# FP_Connectors.net
KiCad netlist of a schematic drawn in Altium Designer
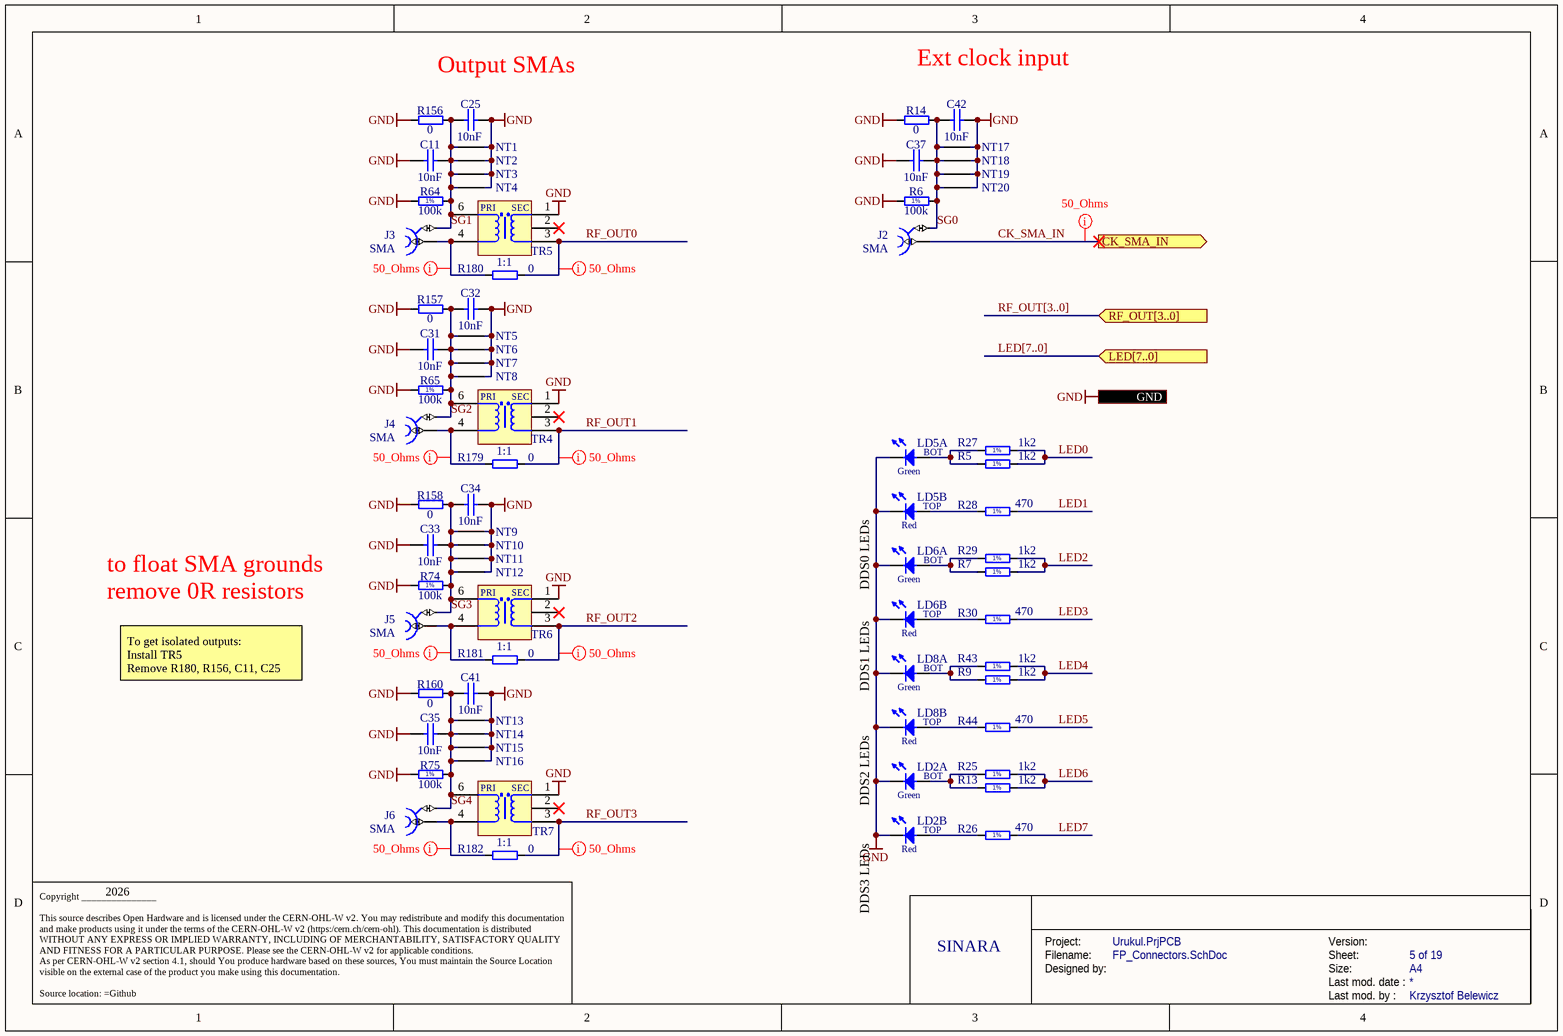
[diagram p0: FP_Connectors.SchDoc]

(export (version "E")
  (design (tool "Eeschema 10.0.6"))
  (components
    (comp (ref "C11")
      (value "10nF")
      (footprint "CAPC1005X55N")
      (description "Non-polarised capacitor")
      (fields
        (field (name "PART NUMBER") "CC0402_10NF_16V_10%_X7R")
        (field (name "VOLTAGE") "16V")
        (field (name "AUTHOR") "CERN DEM JLC")
      )
      (libsource (lib "Capacitors") (part "Capacitor - non polarized"))
    )
    (comp (ref "C25")
      (value "10nF")
      (footprint "CAPC1005X55N")
      (description "Non-polarised capacitor")
      (fields
        (field (name "PART NUMBER") "CC0402_10NF_16V_10%_X7R")
        (field (name "VOLTAGE") "16V")
        (field (name "AUTHOR") "CERN DEM JLC")
      )
      (libsource (lib "Capacitors") (part "Capacitor - non polarized"))
    )
    (comp (ref "C31")
      (value "10nF")
      (footprint "CAPC1005X55N")
      (description "Non-polarised capacitor")
      (fields
        (field (name "PART NUMBER") "CC0402_10NF_16V_10%_X7R")
        (field (name "VOLTAGE") "16V")
        (field (name "AUTHOR") "CERN DEM JLC")
      )
      (libsource (lib "Capacitors") (part "Capacitor - non polarized"))
    )
    (comp (ref "C32")
      (value "10nF")
      (footprint "CAPC1005X55N")
      (description "Non-polarised capacitor")
      (fields
        (field (name "PART NUMBER") "CC0402_10NF_16V_10%_X7R")
        (field (name "VOLTAGE") "16V")
        (field (name "AUTHOR") "CERN DEM JLC")
      )
      (libsource (lib "Capacitors") (part "Capacitor - non polarized"))
    )
    (comp (ref "C33")
      (value "10nF")
      (footprint "CAPC1005X55N")
      (description "Non-polarised capacitor")
      (fields
        (field (name "PART NUMBER") "CC0402_10NF_16V_10%_X7R")
        (field (name "VOLTAGE") "16V")
        (field (name "AUTHOR") "CERN DEM JLC")
      )
      (libsource (lib "Capacitors") (part "Capacitor - non polarized"))
    )
    (comp (ref "C34")
      (value "10nF")
      (footprint "CAPC1005X55N")
      (description "Non-polarised capacitor")
      (fields
        (field (name "PART NUMBER") "CC0402_10NF_16V_10%_X7R")
        (field (name "VOLTAGE") "16V")
        (field (name "AUTHOR") "CERN DEM JLC")
      )
      (libsource (lib "Capacitors") (part "Capacitor - non polarized"))
    )
    (comp (ref "C35")
      (value "10nF")
      (footprint "CAPC1005X55N")
      (description "Non-polarised capacitor")
      (fields
        (field (name "PART NUMBER") "CC0402_10NF_16V_10%_X7R")
        (field (name "VOLTAGE") "16V")
        (field (name "AUTHOR") "CERN DEM JLC")
      )
      (libsource (lib "Capacitors") (part "Capacitor - non polarized"))
    )
    (comp (ref "C37")
      (value "10nF")
      (footprint "CAPC1005X55N")
      (description "Non-polarised capacitor")
      (fields
        (field (name "PART NUMBER") "CC0402_10NF_16V_10%_X7R")
        (field (name "VOLTAGE") "16V")
        (field (name "AUTHOR") "CERN DEM JLC")
      )
      (libsource (lib "Capacitors") (part "Capacitor - non polarized"))
    )
    (comp (ref "C41")
      (value "10nF")
      (footprint "CAPC1005X55N")
      (description "Non-polarised capacitor")
      (fields
        (field (name "PART NUMBER") "CC0402_10NF_16V_10%_X7R")
        (field (name "VOLTAGE") "16V")
        (field (name "AUTHOR") "CERN DEM JLC")
      )
      (libsource (lib "Capacitors") (part "Capacitor - non polarized"))
    )
    (comp (ref "C42")
      (value "10nF")
      (footprint "CAPC1005X55N")
      (description "Non-polarised capacitor")
      (fields
        (field (name "PART NUMBER") "CC0402_10NF_16V_10%_X7R")
        (field (name "VOLTAGE") "16V")
        (field (name "AUTHOR") "CERN DEM JLC")
      )
      (libsource (lib "Capacitors") (part "Capacitor - non polarized"))
    )
    (comp (ref "J2")
      (value "SMA")
      (footprint "DELOCK_65848")
      (description "50 Ohm Through Hole SMA Right Angle PCB Jack")
      (fields
        (field (name "PART NUMBER") "DELOCK_65848")
        (field (name "MANUFACTURER") "DELOCK")
        (field (name "AUTHOR") "GK")
      )
      (libsource (lib "Connectors") (part "CON_SMA_DELOCK_65848"))
    )
    (comp (ref "J3")
      (value "SMA")
      (footprint "DELOCK_65848")
      (description "50 Ohm Through Hole SMA Right Angle PCB Jack")
      (fields
        (field (name "PART NUMBER") "DELOCK_65848")
        (field (name "MANUFACTURER") "DELOCK")
        (field (name "AUTHOR") "GK")
      )
      (libsource (lib "Connectors") (part "CON_SMA_DELOCK_65848"))
    )
    (comp (ref "J4")
      (value "SMA")
      (footprint "DELOCK_65848")
      (description "50 Ohm Through Hole SMA Right Angle PCB Jack")
      (fields
        (field (name "PART NUMBER") "DELOCK_65848")
        (field (name "MANUFACTURER") "DELOCK")
        (field (name "AUTHOR") "GK")
      )
      (libsource (lib "Connectors") (part "CON_SMA_DELOCK_65848"))
    )
    (comp (ref "J5")
      (value "SMA")
      (footprint "DELOCK_65848")
      (description "50 Ohm Through Hole SMA Right Angle PCB Jack")
      (fields
        (field (name "PART NUMBER") "DELOCK_65848")
        (field (name "MANUFACTURER") "DELOCK")
        (field (name "AUTHOR") "GK")
      )
      (libsource (lib "Connectors") (part "CON_SMA_DELOCK_65848"))
    )
    (comp (ref "J6")
      (value "SMA")
      (footprint "DELOCK_65848")
      (description "50 Ohm Through Hole SMA Right Angle PCB Jack")
      (fields
        (field (name "PART NUMBER") "DELOCK_65848")
        (field (name "MANUFACTURER") "DELOCK")
        (field (name "AUTHOR") "GK")
      )
      (libsource (lib "Connectors") (part "CON_SMA_DELOCK_65848"))
    )
    (comp (ref "LD2")
      (value "Red/Green")
      (footprint "LED_DIALIGHT_571-0112F")
      (description "2x LED  Botom Green, Top Red")
      (fields
        (field (name "PART NUMBER") "LED_DIALIGHT_571-0112F")
        (field (name "MANUFACTURER") "DIALIGHT")
        (field (name "AUTHOR") "CERN DEM JLC")
      )
      (libsource (lib "ICs And Semiconductors") (part "LED x2 G-1C2A-BOT_R-3C4A-TOP"))
    )
    (comp (ref "LD5")
      (value "Red/Green")
      (footprint "LED_DIALIGHT_571-0112F")
      (description "2x LED  Botom Green, Top Red")
      (fields
        (field (name "PART NUMBER") "LED_DIALIGHT_571-0112F")
        (field (name "MANUFACTURER") "DIALIGHT")
        (field (name "AUTHOR") "CERN DEM JLC")
      )
      (libsource (lib "ICs And Semiconductors") (part "LED x2 G-1C2A-BOT_R-3C4A-TOP"))
    )
    (comp (ref "LD6")
      (value "Red/Green")
      (footprint "LED_DIALIGHT_571-0112F")
      (description "2x LED  Botom Green, Top Red")
      (fields
        (field (name "PART NUMBER") "LED_DIALIGHT_571-0112F")
        (field (name "MANUFACTURER") "DIALIGHT")
        (field (name "AUTHOR") "CERN DEM JLC")
      )
      (libsource (lib "ICs And Semiconductors") (part "LED x2 G-1C2A-BOT_R-3C4A-TOP"))
    )
    (comp (ref "LD8")
      (value "Red/Green")
      (footprint "LED_DIALIGHT_571-0112F")
      (description "2x LED  Botom Green, Top Red")
      (fields
        (field (name "PART NUMBER") "LED_DIALIGHT_571-0112F")
        (field (name "MANUFACTURER") "DIALIGHT")
        (field (name "AUTHOR") "CERN DEM JLC")
      )
      (libsource (lib "ICs And Semiconductors") (part "LED x2 G-1C2A-BOT_R-3C4A-TOP"))
    )
    (comp (ref "NT1")
      (value "Net Tie")
      (footprint "Net Tie")
      (fields (field (name "AUTHOR") "CERN DEM JLC"))
      (libsource (lib "Eletro-mechanical") (part "Net Tie"))
    )
    (comp (ref "NT2")
      (value "Net Tie")
      (footprint "Net Tie")
      (fields (field (name "AUTHOR") "CERN DEM JLC"))
      (libsource (lib "Eletro-mechanical") (part "Net Tie"))
    )
    (comp (ref "NT3")
      (value "Net Tie")
      (footprint "Net Tie")
      (fields (field (name "AUTHOR") "CERN DEM JLC"))
      (libsource (lib "Eletro-mechanical") (part "Net Tie"))
    )
    (comp (ref "NT4")
      (value "Net Tie")
      (footprint "Net Tie")
      (fields (field (name "AUTHOR") "CERN DEM JLC"))
      (libsource (lib "Eletro-mechanical") (part "Net Tie"))
    )
    (comp (ref "NT5")
      (value "Net Tie")
      (footprint "Net Tie")
      (fields (field (name "AUTHOR") "CERN DEM JLC"))
      (libsource (lib "Eletro-mechanical") (part "Net Tie"))
    )
    (comp (ref "NT6")
      (value "Net Tie")
      (footprint "Net Tie")
      (fields (field (name "AUTHOR") "CERN DEM JLC"))
      (libsource (lib "Eletro-mechanical") (part "Net Tie"))
    )
    (comp (ref "NT7")
      (value "Net Tie")
      (footprint "Net Tie")
      (fields (field (name "AUTHOR") "CERN DEM JLC"))
      (libsource (lib "Eletro-mechanical") (part "Net Tie"))
    )
    (comp (ref "NT8")
      (value "Net Tie")
      (footprint "Net Tie")
      (fields (field (name "AUTHOR") "CERN DEM JLC"))
      (libsource (lib "Eletro-mechanical") (part "Net Tie"))
    )
    (comp (ref "NT9")
      (value "Net Tie")
      (footprint "Net Tie")
      (fields (field (name "AUTHOR") "CERN DEM JLC"))
      (libsource (lib "Eletro-mechanical") (part "Net Tie"))
    )
    (comp (ref "NT10")
      (value "Net Tie")
      (footprint "Net Tie")
      (fields (field (name "AUTHOR") "CERN DEM JLC"))
      (libsource (lib "Eletro-mechanical") (part "Net Tie"))
    )
    (comp (ref "NT11")
      (value "Net Tie")
      (footprint "Net Tie")
      (fields (field (name "AUTHOR") "CERN DEM JLC"))
      (libsource (lib "Eletro-mechanical") (part "Net Tie"))
    )
    (comp (ref "NT12")
      (value "Net Tie")
      (footprint "Net Tie")
      (fields (field (name "AUTHOR") "CERN DEM JLC"))
      (libsource (lib "Eletro-mechanical") (part "Net Tie"))
    )
    (comp (ref "NT13")
      (value "Net Tie")
      (footprint "Net Tie")
      (fields (field (name "AUTHOR") "CERN DEM JLC"))
      (libsource (lib "Eletro-mechanical") (part "Net Tie"))
    )
    (comp (ref "NT14")
      (value "Net Tie")
      (footprint "Net Tie")
      (fields (field (name "AUTHOR") "CERN DEM JLC"))
      (libsource (lib "Eletro-mechanical") (part "Net Tie"))
    )
    (comp (ref "NT15")
      (value "Net Tie")
      (footprint "Net Tie")
      (fields (field (name "AUTHOR") "CERN DEM JLC"))
      (libsource (lib "Eletro-mechanical") (part "Net Tie"))
    )
    (comp (ref "NT16")
      (value "Net Tie")
      (footprint "Net Tie")
      (fields (field (name "AUTHOR") "CERN DEM JLC"))
      (libsource (lib "Eletro-mechanical") (part "Net Tie"))
    )
    (comp (ref "NT17")
      (value "Net Tie")
      (footprint "Net Tie")
      (fields (field (name "AUTHOR") "CERN DEM JLC"))
      (libsource (lib "Eletro-mechanical") (part "Net Tie"))
    )
    (comp (ref "NT18")
      (value "Net Tie")
      (footprint "Net Tie")
      (fields (field (name "AUTHOR") "CERN DEM JLC"))
      (libsource (lib "Eletro-mechanical") (part "Net Tie"))
    )
    (comp (ref "NT19")
      (value "Net Tie")
      (footprint "Net Tie")
      (fields (field (name "AUTHOR") "CERN DEM JLC"))
      (libsource (lib "Eletro-mechanical") (part "Net Tie"))
    )
    (comp (ref "NT20")
      (value "Net Tie")
      (footprint "Net Tie")
      (fields (field (name "AUTHOR") "CERN DEM JLC"))
      (libsource (lib "Eletro-mechanical") (part "Net Tie"))
    )
    (comp (ref "R5")
      (value "1k2")
      (footprint "RESC1608X55N")
      (description "Resistor - 1%")
      (fields
        (field (name "PART NUMBER") "R0603_1K2_1%_0.1W_100PPM")
        (field (name "POWER") "0.1W")
        (field (name "AUTHOR") "CERN DEM JLC")
      )
      (libsource (lib "Resistors") (part "Resistor - 1%"))
    )
    (comp (ref "R6")
      (value "100k")
      (footprint "RESC1005X40N")
      (description "Resistor - 1%")
      (fields
        (field (name "PART NUMBER") "R0402_100K_1%_0.0625W_100PPM")
        (field (name "MANUFACTURER") "GENERIC")
        (field (name "AUTHOR") "CERN DEM JLC")
      )
      (libsource (lib "Resistors") (part "Resistor - 1%"))
    )
    (comp (ref "R7")
      (value "1k2")
      (footprint "RESC1608X55N")
      (description "Resistor - 1%")
      (fields
        (field (name "PART NUMBER") "R0603_1K2_1%_0.1W_100PPM")
        (field (name "POWER") "0.1W")
        (field (name "AUTHOR") "CERN DEM JLC")
      )
      (libsource (lib "Resistors") (part "Resistor - 1%"))
    )
    (comp (ref "R9")
      (value "1k2")
      (footprint "RESC1608X55N")
      (description "Resistor - 1%")
      (fields
        (field (name "PART NUMBER") "R0603_1K2_1%_0.1W_100PPM")
        (field (name "POWER") "0.1W")
        (field (name "AUTHOR") "CERN DEM JLC")
      )
      (libsource (lib "Resistors") (part "Resistor - 1%"))
    )
    (comp (ref "R13")
      (value "1k2")
      (footprint "RESC1608X55N")
      (description "Resistor - 1%")
      (fields
        (field (name "PART NUMBER") "R0603_1K2_1%_0.1W_100PPM")
        (field (name "POWER") "0.1W")
        (field (name "AUTHOR") "CERN DEM JLC")
      )
      (libsource (lib "Resistors") (part "Resistor - 1%"))
    )
    (comp (ref "R14")
      (value "0")
      (footprint "RESC1608X55N")
      (description "Resistor")
      (fields
        (field (name "PART NUMBER") "R0603_0R_JUMPER")
        (field (name "MANUFACTURER") "GENERIC")
        (field (name "AUTHOR") "CERN DEM JLC")
      )
      (libsource (lib "Resistors") (part "Resistor"))
    )
    (comp (ref "R25")
      (value "1k2")
      (footprint "RESC1608X55N")
      (description "Resistor - 1%")
      (fields
        (field (name "PART NUMBER") "R0603_1K2_1%_0.1W_100PPM")
        (field (name "POWER") "0.1W")
        (field (name "AUTHOR") "CERN DEM JLC")
      )
      (libsource (lib "Resistors") (part "Resistor - 1%"))
    )
    (comp (ref "R26")
      (value "470")
      (footprint "RESC1005X40N")
      (description "Resistor - 1%")
      (fields
        (field (name "PART NUMBER") "R0402_470R_1%_0.0625W_100PPM")
        (field (name "POWER") "0.0625W")
        (field (name "AUTHOR") "CERN DEM JLC")
      )
      (libsource (lib "Resistors") (part "Resistor - 1%"))
    )
    (comp (ref "R27")
      (value "1k2")
      (footprint "RESC1608X55N")
      (description "Resistor - 1%")
      (fields
        (field (name "PART NUMBER") "R0603_1K2_1%_0.1W_100PPM")
        (field (name "POWER") "0.1W")
        (field (name "AUTHOR") "CERN DEM JLC")
      )
      (libsource (lib "Resistors") (part "Resistor - 1%"))
    )
    (comp (ref "R28")
      (value "470")
      (footprint "RESC1005X40N")
      (description "Resistor - 1%")
      (fields
        (field (name "PART NUMBER") "R0402_470R_1%_0.0625W_100PPM")
        (field (name "POWER") "0.0625W")
        (field (name "AUTHOR") "CERN DEM JLC")
      )
      (libsource (lib "Resistors") (part "Resistor - 1%"))
    )
    (comp (ref "R29")
      (value "1k2")
      (footprint "RESC1608X55N")
      (description "Resistor - 1%")
      (fields
        (field (name "PART NUMBER") "R0603_1K2_1%_0.1W_100PPM")
        (field (name "POWER") "0.1W")
        (field (name "AUTHOR") "CERN DEM JLC")
      )
      (libsource (lib "Resistors") (part "Resistor - 1%"))
    )
    (comp (ref "R30")
      (value "470")
      (footprint "RESC1005X40N")
      (description "Resistor - 1%")
      (fields
        (field (name "PART NUMBER") "R0402_470R_1%_0.0625W_100PPM")
        (field (name "POWER") "0.0625W")
        (field (name "AUTHOR") "CERN DEM JLC")
      )
      (libsource (lib "Resistors") (part "Resistor - 1%"))
    )
    (comp (ref "R43")
      (value "1k2")
      (footprint "RESC1608X55N")
      (description "Resistor - 1%")
      (fields
        (field (name "PART NUMBER") "R0603_1K2_1%_0.1W_100PPM")
        (field (name "POWER") "0.1W")
        (field (name "AUTHOR") "CERN DEM JLC")
      )
      (libsource (lib "Resistors") (part "Resistor - 1%"))
    )
    (comp (ref "R44")
      (value "470")
      (footprint "RESC1005X40N")
      (description "Resistor - 1%")
      (fields
        (field (name "PART NUMBER") "R0402_470R_1%_0.0625W_100PPM")
        (field (name "POWER") "0.0625W")
        (field (name "AUTHOR") "CERN DEM JLC")
      )
      (libsource (lib "Resistors") (part "Resistor - 1%"))
    )
    (comp (ref "R64")
      (value "100k")
      (footprint "RESC1005X40N")
      (description "Resistor - 1%")
      (fields
        (field (name "PART NUMBER") "R0402_100K_1%_0.0625W_100PPM")
        (field (name "MANUFACTURER") "GENERIC")
        (field (name "AUTHOR") "CERN DEM JLC")
      )
      (libsource (lib "Resistors") (part "Resistor - 1%"))
    )
    (comp (ref "R65")
      (value "100k")
      (footprint "RESC1005X40N")
      (description "Resistor - 1%")
      (fields
        (field (name "PART NUMBER") "R0402_100K_1%_0.0625W_100PPM")
        (field (name "MANUFACTURER") "GENERIC")
        (field (name "AUTHOR") "CERN DEM JLC")
      )
      (libsource (lib "Resistors") (part "Resistor - 1%"))
    )
    (comp (ref "R74")
      (value "100k")
      (footprint "RESC1005X40N")
      (description "Resistor - 1%")
      (fields
        (field (name "PART NUMBER") "R0402_100K_1%_0.0625W_100PPM")
        (field (name "MANUFACTURER") "GENERIC")
        (field (name "AUTHOR") "CERN DEM JLC")
      )
      (libsource (lib "Resistors") (part "Resistor - 1%"))
    )
    (comp (ref "R75")
      (value "100k")
      (footprint "RESC1005X40N")
      (description "Resistor - 1%")
      (fields
        (field (name "PART NUMBER") "R0402_100K_1%_0.0625W_100PPM")
        (field (name "MANUFACTURER") "GENERIC")
        (field (name "AUTHOR") "CERN DEM JLC")
      )
      (libsource (lib "Resistors") (part "Resistor - 1%"))
    )
    (comp (ref "R156")
      (value "0")
      (footprint "RESC1608X55N")
      (description "Resistor")
      (fields
        (field (name "PART NUMBER") "R0603_0R_JUMPER")
        (field (name "MANUFACTURER") "GENERIC")
        (field (name "AUTHOR") "CERN DEM JLC")
      )
      (libsource (lib "Resistors") (part "Resistor"))
    )
    (comp (ref "R157")
      (value "0")
      (footprint "RESC1608X55N")
      (description "Resistor")
      (fields
        (field (name "PART NUMBER") "R0603_0R_JUMPER")
        (field (name "MANUFACTURER") "GENERIC")
        (field (name "AUTHOR") "CERN DEM JLC")
      )
      (libsource (lib "Resistors") (part "Resistor"))
    )
    (comp (ref "R158")
      (value "0")
      (footprint "RESC1608X55N")
      (description "Resistor")
      (fields
        (field (name "PART NUMBER") "R0603_0R_JUMPER")
        (field (name "MANUFACTURER") "GENERIC")
        (field (name "AUTHOR") "CERN DEM JLC")
      )
      (libsource (lib "Resistors") (part "Resistor"))
    )
    (comp (ref "R160")
      (value "0")
      (footprint "RESC1608X55N")
      (description "Resistor")
      (fields
        (field (name "PART NUMBER") "R0603_0R_JUMPER")
        (field (name "MANUFACTURER") "GENERIC")
        (field (name "AUTHOR") "CERN DEM JLC")
      )
      (libsource (lib "Resistors") (part "Resistor"))
    )
    (comp (ref "R179")
      (value "0")
      (footprint "RESC1005X40N")
      (description "Resistor")
      (fields
        (field (name "PART NUMBER") "R0402_0R_JUMPER")
        (field (name "MANUFACTURER") "GENERIC")
        (field (name "AUTHOR") "CERN DEM JLC")
      )
      (libsource (lib "Resistors") (part "Resistor"))
    )
    (comp (ref "R180")
      (value "0")
      (footprint "RESC1005X40N")
      (description "Resistor")
      (fields
        (field (name "PART NUMBER") "R0402_0R_JUMPER")
        (field (name "MANUFACTURER") "GENERIC")
        (field (name "AUTHOR") "CERN DEM JLC")
      )
      (libsource (lib "Resistors") (part "Resistor"))
    )
    (comp (ref "R181")
      (value "0")
      (footprint "RESC1005X40N")
      (description "Resistor")
      (fields
        (field (name "PART NUMBER") "R0402_0R_JUMPER")
        (field (name "MANUFACTURER") "GENERIC")
        (field (name "AUTHOR") "CERN DEM JLC")
      )
      (libsource (lib "Resistors") (part "Resistor"))
    )
    (comp (ref "R182")
      (value "0")
      (footprint "RESC1005X40N")
      (description "Resistor")
      (fields
        (field (name "PART NUMBER") "R0402_0R_JUMPER")
        (field (name "MANUFACTURER") "GENERIC")
        (field (name "AUTHOR") "CERN DEM JLC")
      )
      (libsource (lib "Resistors") (part "Resistor"))
    )
    (comp (ref "TR4")
      (value "1:1")
      (footprint "XFMR_MINI-CIRCUITS_AT224-1")
      (description "50 Ohm 1.5 To 500MHz RF Transformers")
      (fields
        (field (name "PART NUMBER") "XFMR_MINI-CIRCUITS_TC1-1+")
        (field (name "MANUFACTURER") "MINI-CIRCUITS")
        (field (name "AUTHOR") "CERN DEM JLC")
      )
      (libsource (lib "Inductors & Transformers") (part "XFMR_MINI-CIRCUITS_TC1-1+"))
    )
    (comp (ref "TR5")
      (value "1:1")
      (footprint "XFMR_MINI-CIRCUITS_AT224-1")
      (description "50 Ohm 1.5 To 500MHz RF Transformers")
      (fields
        (field (name "PART NUMBER") "XFMR_MINI-CIRCUITS_TC1-1+")
        (field (name "MANUFACTURER") "MINI-CIRCUITS")
        (field (name "AUTHOR") "CERN DEM JLC")
      )
      (libsource (lib "Inductors & Transformers") (part "XFMR_MINI-CIRCUITS_TC1-1+"))
    )
    (comp (ref "TR6")
      (value "1:1")
      (footprint "XFMR_MINI-CIRCUITS_AT224-1")
      (description "50 Ohm 1.5 To 500MHz RF Transformers")
      (fields
        (field (name "PART NUMBER") "XFMR_MINI-CIRCUITS_TC1-1+")
        (field (name "MANUFACTURER") "MINI-CIRCUITS")
        (field (name "AUTHOR") "CERN DEM JLC")
      )
      (libsource (lib "Inductors & Transformers") (part "XFMR_MINI-CIRCUITS_TC1-1+"))
    )
    (comp (ref "TR7")
      (value "1:1")
      (footprint "XFMR_MINI-CIRCUITS_AT224-1")
      (description "50 Ohm 1.5 To 500MHz RF Transformers")
      (fields
        (field (name "PART NUMBER") "XFMR_MINI-CIRCUITS_TC1-1+")
        (field (name "MANUFACTURER") "MINI-CIRCUITS")
        (field (name "AUTHOR") "CERN DEM JLC")
      )
      (libsource (lib "Inductors & Transformers") (part "XFMR_MINI-CIRCUITS_TC1-1+"))
    )
  )
  (nets
    (net (code "1") (name "/CK_SMA_IN") (class "Default")
      (node (ref "J2") (pin "1") (pinfunction "1_1") (pintype "bidirectional+no_connect"))
    )
    (net (code "2") (name "/LED0") (class "Default")
      (node (ref "R27") (pin "2") (pinfunction "2_2") (pintype "passive"))
      (node (ref "R5") (pin "2") (pinfunction "2_2") (pintype "passive"))
    )
    (net (code "3") (name "/LED1") (class "Default")
      (node (ref "R28") (pin "1") (pinfunction "1_1") (pintype "passive"))
    )
    (net (code "4") (name "/LED2") (class "Default")
      (node (ref "R29") (pin "2") (pinfunction "2_2") (pintype "passive"))
      (node (ref "R7") (pin "2") (pinfunction "2_2") (pintype "passive"))
    )
    (net (code "5") (name "/LED3") (class "Default")
      (node (ref "R30") (pin "1") (pinfunction "1_1") (pintype "passive"))
    )
    (net (code "6") (name "/LED4") (class "Default")
      (node (ref "R43") (pin "2") (pinfunction "2_2") (pintype "passive"))
      (node (ref "R9") (pin "2") (pinfunction "2_2") (pintype "passive"))
    )
    (net (code "7") (name "/LED5") (class "Default")
      (node (ref "R44") (pin "1") (pinfunction "1_1") (pintype "passive"))
    )
    (net (code "8") (name "/LED6") (class "Default")
      (node (ref "R13") (pin "2") (pinfunction "2_2") (pintype "passive"))
      (node (ref "R25") (pin "2") (pinfunction "2_2") (pintype "passive"))
    )
    (net (code "9") (name "/LED7") (class "Default")
      (node (ref "R26") (pin "1") (pinfunction "1_1") (pintype "passive"))
    )
    (net (code "11") (name "/RF_OUT0") (class "Default")
      (node (ref "R180") (pin "2") (pinfunction "2_2") (pintype "passive"))
      (node (ref "TR5") (pin "3") (pinfunction "S_3") (pintype "passive"))
    )
    (net (code "12") (name "/RF_OUT1") (class "Default")
      (node (ref "R179") (pin "2") (pinfunction "2_2") (pintype "passive"))
      (node (ref "TR4") (pin "3") (pinfunction "S_3") (pintype "passive"))
    )
    (net (code "13") (name "/RF_OUT2") (class "Default")
      (node (ref "R181") (pin "2") (pinfunction "2_2") (pintype "passive"))
      (node (ref "TR6") (pin "3") (pinfunction "S_3") (pintype "passive"))
    )
    (net (code "14") (name "/RF_OUT3") (class "Default")
      (node (ref "R182") (pin "2") (pinfunction "2_2") (pintype "passive"))
      (node (ref "TR7") (pin "3") (pinfunction "S_3") (pintype "passive"))
    )
    (net (code "16") (name "/SG0") (class "Default")
      (node (ref "C37") (pin "1") (pinfunction "1_1") (pintype "passive"))
      (node (ref "C42") (pin "2") (pinfunction "2_2") (pintype "passive"))
      (node (ref "J2") (pin "2") (pinfunction "2_2") (pintype "bidirectional"))
      (node (ref "NT17") (pin "1") (pinfunction "1_1") (pintype "bidirectional"))
      (node (ref "NT18") (pin "1") (pinfunction "1_1") (pintype "bidirectional"))
      (node (ref "NT19") (pin "1") (pinfunction "1_1") (pintype "bidirectional"))
      (node (ref "NT20") (pin "1") (pinfunction "1_1") (pintype "bidirectional"))
      (node (ref "R14") (pin "2") (pinfunction "2_2") (pintype "passive"))
      (node (ref "R6") (pin "2") (pinfunction "2_2") (pintype "passive"))
    )
    (net (code "17") (name "/SG1") (class "Default")
      (node (ref "C11") (pin "1") (pinfunction "1_1") (pintype "passive"))
      (node (ref "C25") (pin "2") (pinfunction "2_2") (pintype "passive"))
      (node (ref "J3") (pin "2") (pinfunction "2_2") (pintype "bidirectional"))
      (node (ref "NT1") (pin "1") (pinfunction "1_1") (pintype "bidirectional"))
      (node (ref "NT2") (pin "1") (pinfunction "1_1") (pintype "bidirectional"))
      (node (ref "NT3") (pin "1") (pinfunction "1_1") (pintype "bidirectional"))
      (node (ref "NT4") (pin "1") (pinfunction "1_1") (pintype "bidirectional"))
      (node (ref "R156") (pin "2") (pinfunction "2_2") (pintype "passive"))
      (node (ref "R64") (pin "2") (pinfunction "2_2") (pintype "passive"))
      (node (ref "TR5") (pin "6") (pinfunction "PDOT_6") (pintype "passive"))
    )
    (net (code "18") (name "/SG2") (class "Default")
      (node (ref "C31") (pin "1") (pinfunction "1_1") (pintype "passive"))
      (node (ref "C32") (pin "2") (pinfunction "2_2") (pintype "passive"))
      (node (ref "J4") (pin "2") (pinfunction "2_2") (pintype "bidirectional"))
      (node (ref "NT5") (pin "1") (pinfunction "1_1") (pintype "bidirectional"))
      (node (ref "NT6") (pin "1") (pinfunction "1_1") (pintype "bidirectional"))
      (node (ref "NT7") (pin "1") (pinfunction "1_1") (pintype "bidirectional"))
      (node (ref "NT8") (pin "1") (pinfunction "1_1") (pintype "bidirectional"))
      (node (ref "R157") (pin "2") (pinfunction "2_2") (pintype "passive"))
      (node (ref "R65") (pin "2") (pinfunction "2_2") (pintype "passive"))
      (node (ref "TR4") (pin "6") (pinfunction "PDOT_6") (pintype "passive"))
    )
    (net (code "19") (name "/SG3") (class "Default")
      (node (ref "C33") (pin "1") (pinfunction "1_1") (pintype "passive"))
      (node (ref "C34") (pin "2") (pinfunction "2_2") (pintype "passive"))
      (node (ref "J5") (pin "2") (pinfunction "2_2") (pintype "bidirectional"))
      (node (ref "NT10") (pin "1") (pinfunction "1_1") (pintype "bidirectional"))
      (node (ref "NT11") (pin "1") (pinfunction "1_1") (pintype "bidirectional"))
      (node (ref "NT12") (pin "1") (pinfunction "1_1") (pintype "bidirectional"))
      (node (ref "NT9") (pin "1") (pinfunction "1_1") (pintype "bidirectional"))
      (node (ref "R158") (pin "2") (pinfunction "2_2") (pintype "passive"))
      (node (ref "R74") (pin "2") (pinfunction "2_2") (pintype "passive"))
      (node (ref "TR6") (pin "6") (pinfunction "PDOT_6") (pintype "passive"))
    )
    (net (code "20") (name "/SG4") (class "Default")
      (node (ref "C35") (pin "1") (pinfunction "1_1") (pintype "passive"))
      (node (ref "C41") (pin "2") (pinfunction "2_2") (pintype "passive"))
      (node (ref "J6") (pin "2") (pinfunction "2_2") (pintype "bidirectional"))
      (node (ref "NT13") (pin "1") (pinfunction "1_1") (pintype "bidirectional"))
      (node (ref "NT14") (pin "1") (pinfunction "1_1") (pintype "bidirectional"))
      (node (ref "NT15") (pin "1") (pinfunction "1_1") (pintype "bidirectional"))
      (node (ref "NT16") (pin "1") (pinfunction "1_1") (pintype "bidirectional"))
      (node (ref "R160") (pin "2") (pinfunction "2_2") (pintype "passive"))
      (node (ref "R75") (pin "2") (pinfunction "2_2") (pintype "passive"))
      (node (ref "TR7") (pin "6") (pinfunction "PDOT_6") (pintype "passive"))
    )
    (net (code "21") (name "GND") (class "Default")
      (node (ref "C11") (pin "2") (pinfunction "2_2") (pintype "passive"))
      (node (ref "C25") (pin "1") (pinfunction "1_1") (pintype "passive"))
      (node (ref "C31") (pin "2") (pinfunction "2_2") (pintype "passive"))
      (node (ref "C32") (pin "1") (pinfunction "1_1") (pintype "passive"))
      (node (ref "C33") (pin "2") (pinfunction "2_2") (pintype "passive"))
      (node (ref "C34") (pin "1") (pinfunction "1_1") (pintype "passive"))
      (node (ref "C35") (pin "2") (pinfunction "2_2") (pintype "passive"))
      (node (ref "C37") (pin "2") (pinfunction "2_2") (pintype "passive"))
      (node (ref "C41") (pin "1") (pinfunction "1_1") (pintype "passive"))
      (node (ref "C42") (pin "1") (pinfunction "1_1") (pintype "passive"))
      (node (ref "LD2") (pin "1") (pinfunction "C_1") (pintype "passive"))
      (node (ref "LD2") (pin "3") (pinfunction "C_3") (pintype "passive"))
      (node (ref "LD5") (pin "1") (pinfunction "C_1") (pintype "passive"))
      (node (ref "LD5") (pin "3") (pinfunction "C_3") (pintype "passive"))
      (node (ref "LD6") (pin "1") (pinfunction "C_1") (pintype "passive"))
      (node (ref "LD6") (pin "3") (pinfunction "C_3") (pintype "passive"))
      (node (ref "LD8") (pin "1") (pinfunction "C_1") (pintype "passive"))
      (node (ref "LD8") (pin "3") (pinfunction "C_3") (pintype "passive"))
      (node (ref "NT1") (pin "2") (pinfunction "2_2") (pintype "bidirectional"))
      (node (ref "NT10") (pin "2") (pinfunction "2_2") (pintype "bidirectional"))
      (node (ref "NT11") (pin "2") (pinfunction "2_2") (pintype "bidirectional"))
      (node (ref "NT12") (pin "2") (pinfunction "2_2") (pintype "bidirectional"))
      (node (ref "NT13") (pin "2") (pinfunction "2_2") (pintype "bidirectional"))
      (node (ref "NT14") (pin "2") (pinfunction "2_2") (pintype "bidirectional"))
      (node (ref "NT15") (pin "2") (pinfunction "2_2") (pintype "bidirectional"))
      (node (ref "NT16") (pin "2") (pinfunction "2_2") (pintype "bidirectional"))
      (node (ref "NT17") (pin "2") (pinfunction "2_2") (pintype "bidirectional"))
      (node (ref "NT18") (pin "2") (pinfunction "2_2") (pintype "bidirectional"))
      (node (ref "NT19") (pin "2") (pinfunction "2_2") (pintype "bidirectional"))
      (node (ref "NT2") (pin "2") (pinfunction "2_2") (pintype "bidirectional"))
      (node (ref "NT20") (pin "2") (pinfunction "2_2") (pintype "bidirectional"))
      (node (ref "NT3") (pin "2") (pinfunction "2_2") (pintype "bidirectional"))
      (node (ref "NT4") (pin "2") (pinfunction "2_2") (pintype "bidirectional"))
      (node (ref "NT5") (pin "2") (pinfunction "2_2") (pintype "bidirectional"))
      (node (ref "NT6") (pin "2") (pinfunction "2_2") (pintype "bidirectional"))
      (node (ref "NT7") (pin "2") (pinfunction "2_2") (pintype "bidirectional"))
      (node (ref "NT8") (pin "2") (pinfunction "2_2") (pintype "bidirectional"))
      (node (ref "NT9") (pin "2") (pinfunction "2_2") (pintype "bidirectional"))
      (node (ref "R14") (pin "1") (pinfunction "1_1") (pintype "passive"))
      (node (ref "R156") (pin "1") (pinfunction "1_1") (pintype "passive"))
      (node (ref "R157") (pin "1") (pinfunction "1_1") (pintype "passive"))
      (node (ref "R158") (pin "1") (pinfunction "1_1") (pintype "passive"))
      (node (ref "R160") (pin "1") (pinfunction "1_1") (pintype "passive"))
      (node (ref "R6") (pin "1") (pinfunction "1_1") (pintype "passive"))
      (node (ref "R64") (pin "1") (pinfunction "1_1") (pintype "passive"))
      (node (ref "R65") (pin "1") (pinfunction "1_1") (pintype "passive"))
      (node (ref "R74") (pin "1") (pinfunction "1_1") (pintype "passive"))
      (node (ref "R75") (pin "1") (pinfunction "1_1") (pintype "passive"))
      (node (ref "TR4") (pin "1") (pinfunction "SDOT_1") (pintype "passive"))
      (node (ref "TR5") (pin "1") (pinfunction "SDOT_1") (pintype "passive"))
      (node (ref "TR6") (pin "1") (pinfunction "SDOT_1") (pintype "passive"))
      (node (ref "TR7") (pin "1") (pinfunction "SDOT_1") (pintype "passive"))
    )
    (net (code "22") (name "Net-(LD2A-A)") (class "Default")
      (node (ref "LD2") (pin "2") (pinfunction "A_2") (pintype "passive"))
      (node (ref "R13") (pin "1") (pinfunction "1_1") (pintype "passive"))
      (node (ref "R25") (pin "1") (pinfunction "1_1") (pintype "passive"))
    )
    (net (code "23") (name "Net-(LD2B-A)") (class "Default")
      (node (ref "LD2") (pin "4") (pinfunction "A_4") (pintype "passive"))
      (node (ref "R26") (pin "2") (pinfunction "2_2") (pintype "passive"))
    )
    (net (code "24") (name "Net-(LD5A-A)") (class "Default")
      (node (ref "LD5") (pin "2") (pinfunction "A_2") (pintype "passive"))
      (node (ref "R27") (pin "1") (pinfunction "1_1") (pintype "passive"))
      (node (ref "R5") (pin "1") (pinfunction "1_1") (pintype "passive"))
    )
    (net (code "25") (name "Net-(LD5B-A)") (class "Default")
      (node (ref "LD5") (pin "4") (pinfunction "A_4") (pintype "passive"))
      (node (ref "R28") (pin "2") (pinfunction "2_2") (pintype "passive"))
    )
    (net (code "26") (name "Net-(LD6A-A)") (class "Default")
      (node (ref "LD6") (pin "2") (pinfunction "A_2") (pintype "passive"))
      (node (ref "R29") (pin "1") (pinfunction "1_1") (pintype "passive"))
      (node (ref "R7") (pin "1") (pinfunction "1_1") (pintype "passive"))
    )
    (net (code "27") (name "Net-(LD6B-A)") (class "Default")
      (node (ref "LD6") (pin "4") (pinfunction "A_4") (pintype "passive"))
      (node (ref "R30") (pin "2") (pinfunction "2_2") (pintype "passive"))
    )
    (net (code "28") (name "Net-(LD8A-A)") (class "Default")
      (node (ref "LD8") (pin "2") (pinfunction "A_2") (pintype "passive"))
      (node (ref "R43") (pin "1") (pinfunction "1_1") (pintype "passive"))
      (node (ref "R9") (pin "1") (pinfunction "1_1") (pintype "passive"))
    )
    (net (code "29") (name "Net-(LD8B-A)") (class "Default")
      (node (ref "LD8") (pin "4") (pinfunction "A_4") (pintype "passive"))
      (node (ref "R44") (pin "2") (pinfunction "2_2") (pintype "passive"))
    )
    (net (code "30") (name "Net-(TR4-P)") (class "Default")
      (node (ref "J4") (pin "1") (pinfunction "1_1") (pintype "bidirectional"))
      (node (ref "R179") (pin "1") (pinfunction "1_1") (pintype "passive"))
      (node (ref "TR4") (pin "4") (pinfunction "P_4") (pintype "passive"))
    )
    (net (code "31") (name "Net-(TR5-P)") (class "Default")
      (node (ref "J3") (pin "1") (pinfunction "1_1") (pintype "bidirectional"))
      (node (ref "R180") (pin "1") (pinfunction "1_1") (pintype "passive"))
      (node (ref "TR5") (pin "4") (pinfunction "P_4") (pintype "passive"))
    )
    (net (code "32") (name "Net-(TR6-P)") (class "Default")
      (node (ref "J5") (pin "1") (pinfunction "1_1") (pintype "bidirectional"))
      (node (ref "R181") (pin "1") (pinfunction "1_1") (pintype "passive"))
      (node (ref "TR6") (pin "4") (pinfunction "P_4") (pintype "passive"))
    )
    (net (code "33") (name "Net-(TR7-P)") (class "Default")
      (node (ref "J6") (pin "1") (pinfunction "1_1") (pintype "bidirectional"))
      (node (ref "R182") (pin "1") (pinfunction "1_1") (pintype "passive"))
      (node (ref "TR7") (pin "4") (pinfunction "P_4") (pintype "passive"))
    )
    (net (code "34") (name "unconnected-(TR4-NU-Pad2)") (class "Default")
      (node (ref "TR4") (pin "2") (pinfunction "NU_2") (pintype "passive+no_connect"))
    )
    (net (code "35") (name "unconnected-(TR5-NU-Pad2)") (class "Default")
      (node (ref "TR5") (pin "2") (pinfunction "NU_2") (pintype "passive+no_connect"))
    )
    (net (code "36") (name "unconnected-(TR6-NU-Pad2)") (class "Default")
      (node (ref "TR6") (pin "2") (pinfunction "NU_2") (pintype "passive+no_connect"))
    )
    (net (code "37") (name "unconnected-(TR7-NU-Pad2)") (class "Default")
      (node (ref "TR7") (pin "2") (pinfunction "NU_2") (pintype "passive+no_connect"))
    )
  )
)
